# Nano_CAN_shield_v0_1.net
KiCad netlist of a schematic drawn in EAGLE
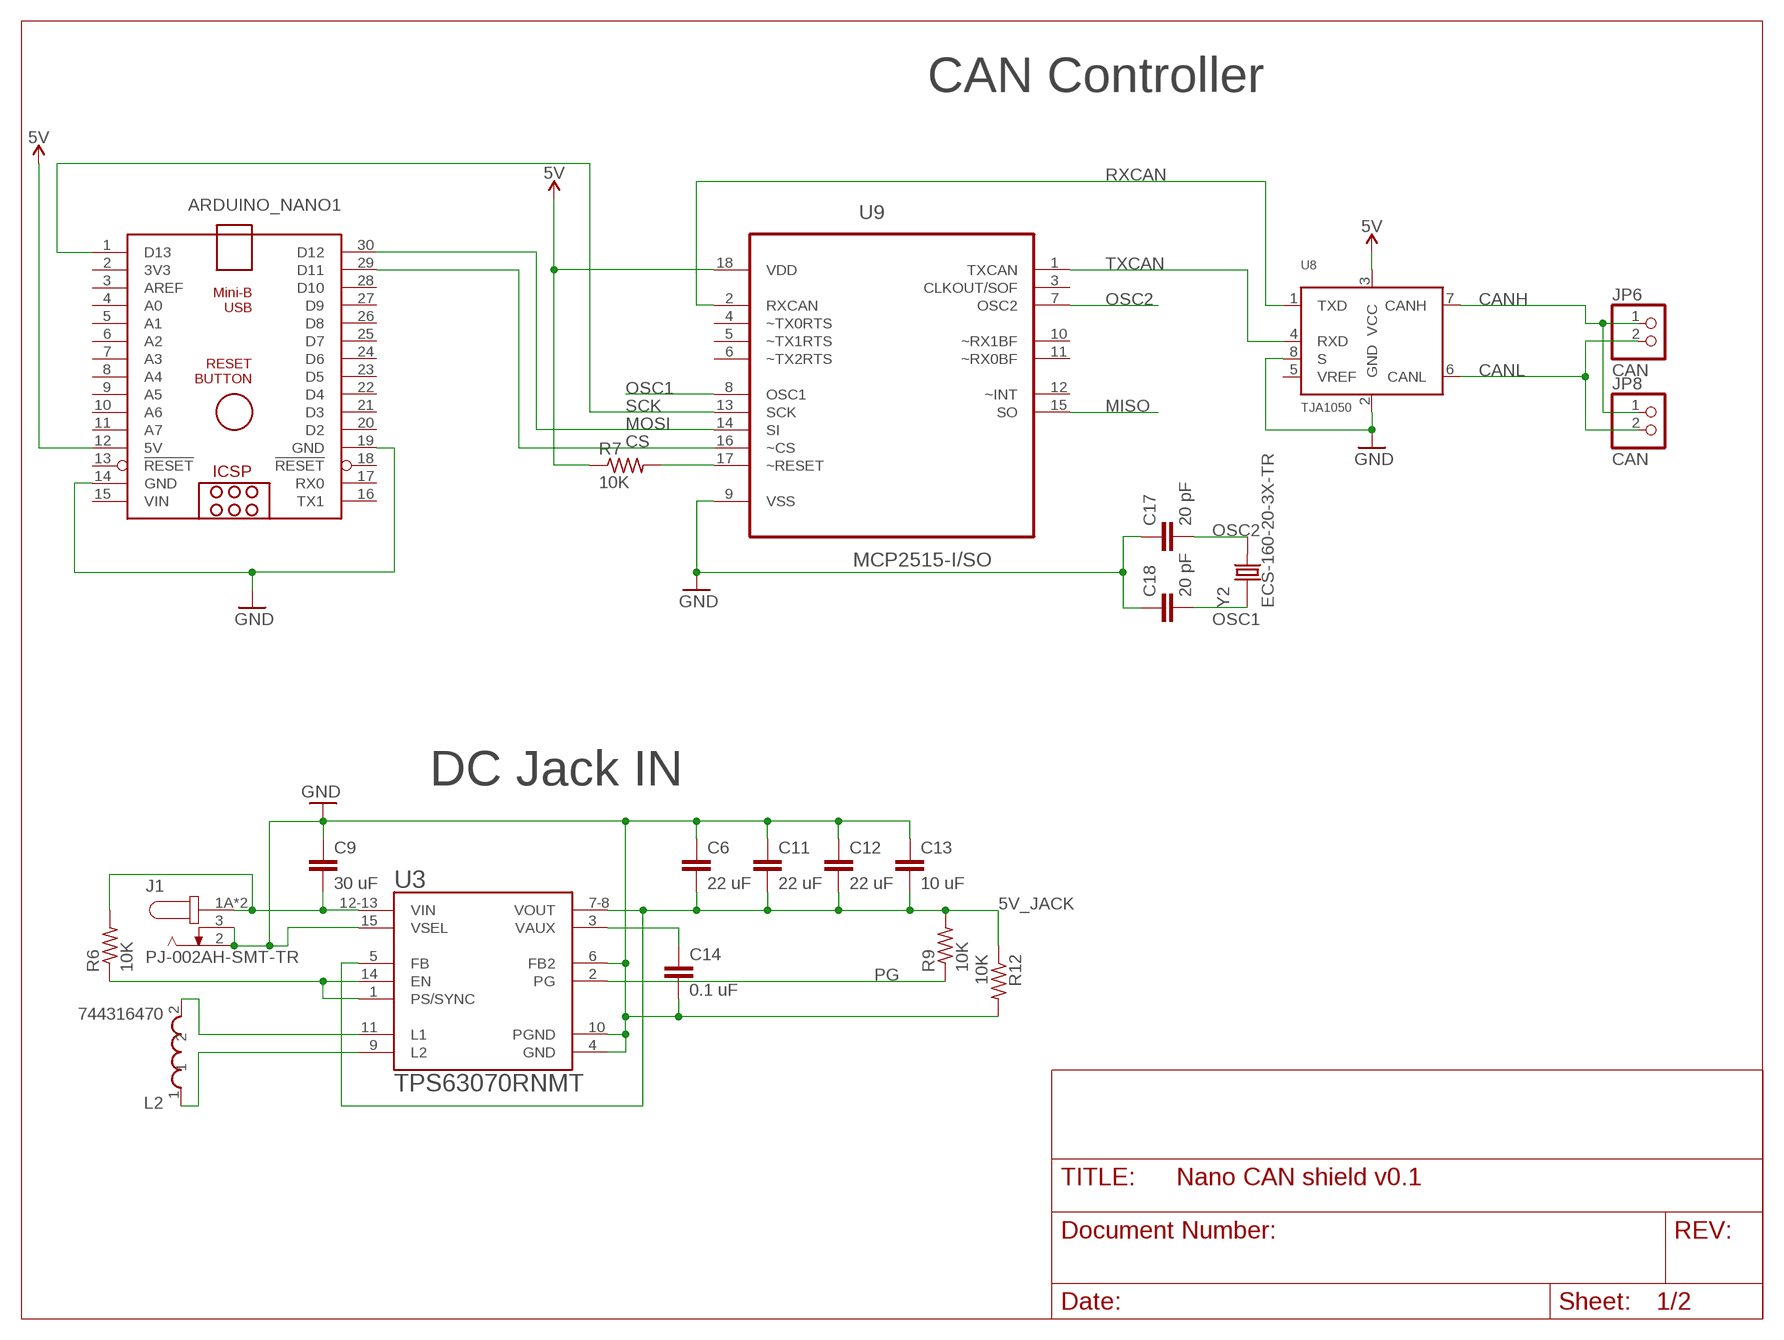
[diagram p0: schematic, sheet 1]
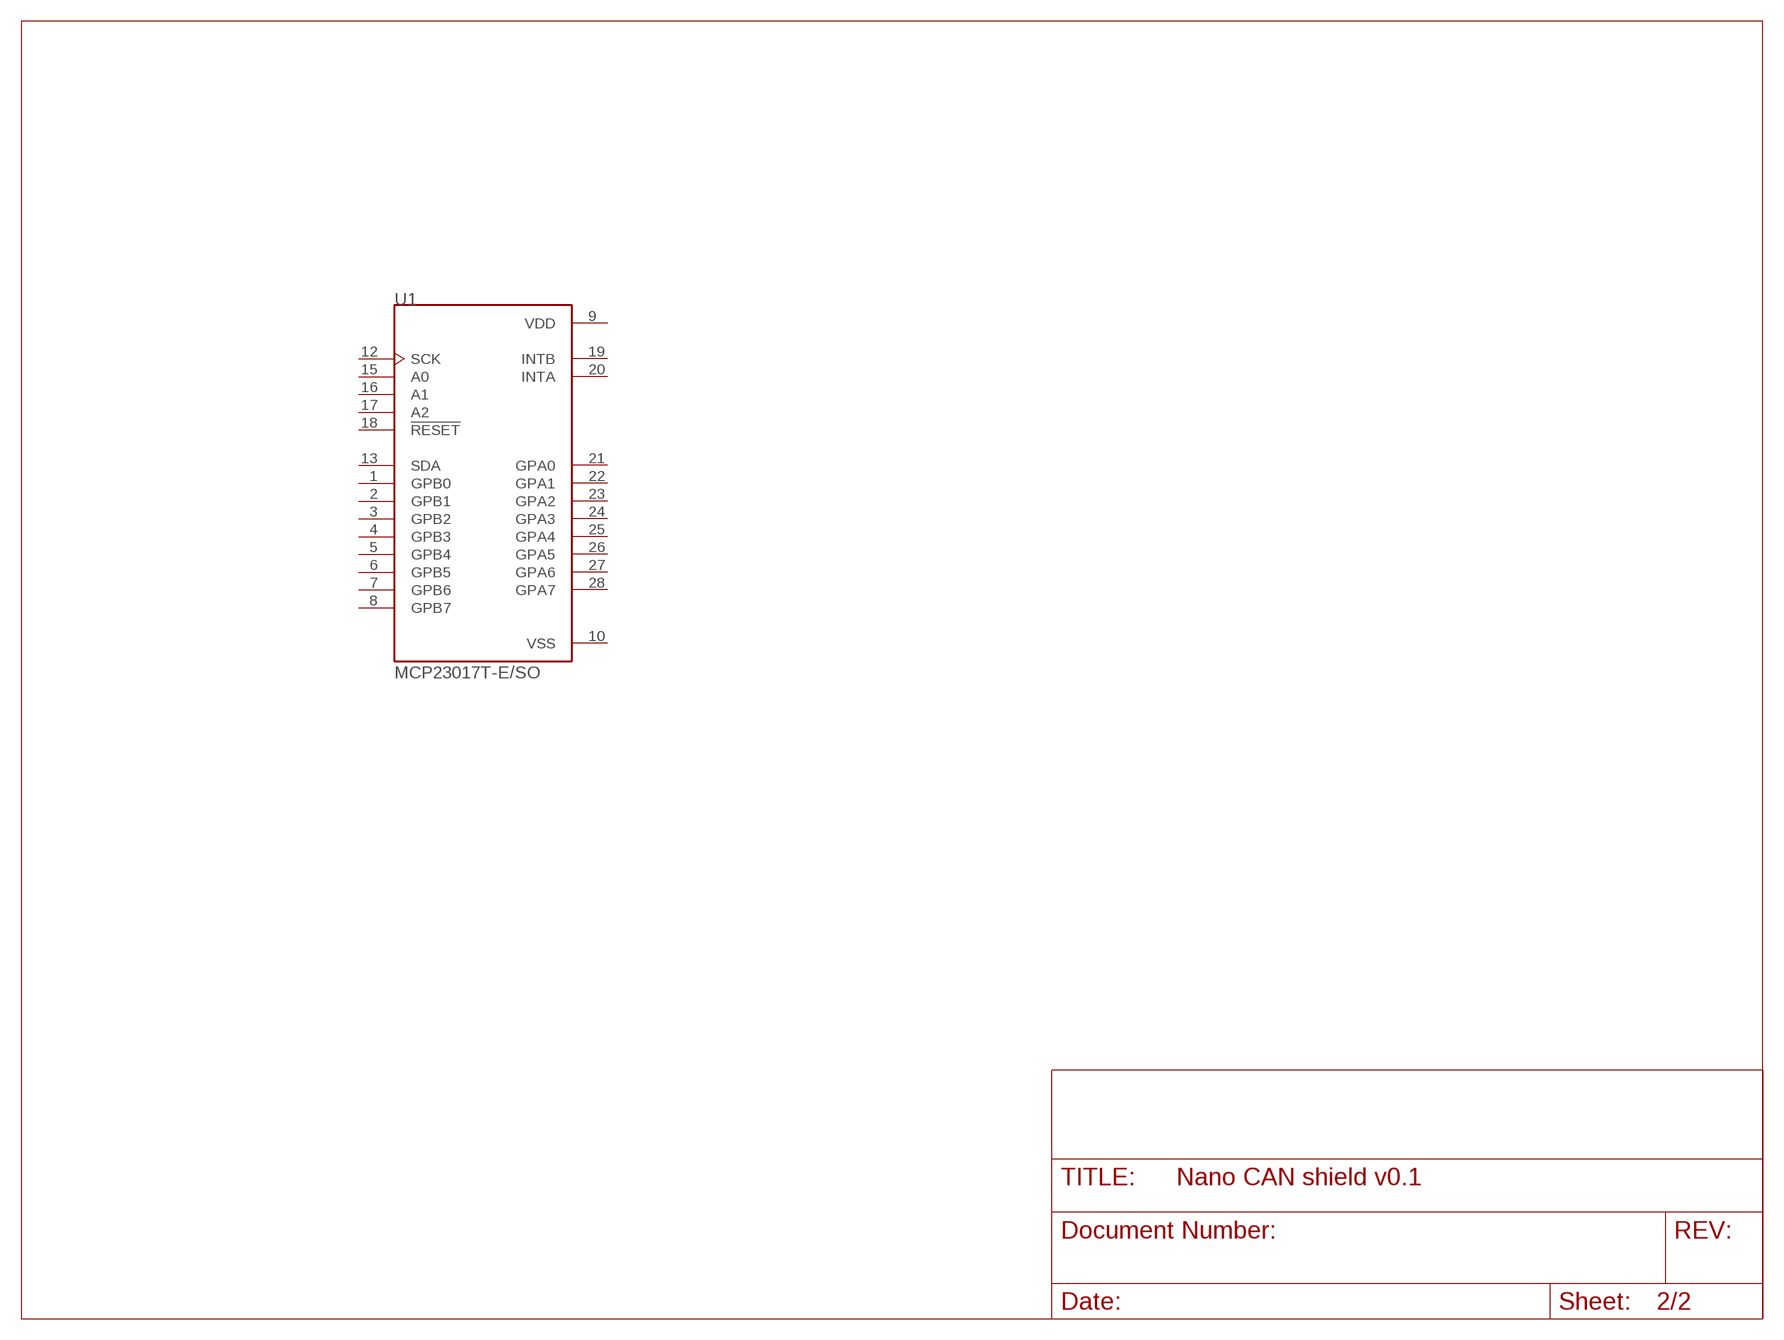
[diagram p1: schematic, sheet 2]

(export (version "E")
  (design (tool "Eeschema 10.0.6"))
  (components
    (comp (ref "ARDUINO_NANO1")
      (value "ARDUINO_NANO")
      (footprint "eagle-import:ARDUINO_NANO")
      (libsource (lib "eagle-import") (part "ARDUINO_NANO"))
    )
    (comp (ref "C6")
      (value "22 uF")
      (footprint "eagle-import:C0603")
      (libsource (lib "eagle-import") (part "C-EUC0603"))
    )
    (comp (ref "C9")
      (value "30 uF")
      (footprint "eagle-import:C0603")
      (libsource (lib "eagle-import") (part "C-EUC0603"))
    )
    (comp (ref "C11")
      (value "22 uF")
      (footprint "eagle-import:C0603")
      (libsource (lib "eagle-import") (part "C-EUC0603"))
    )
    (comp (ref "C12")
      (value "22 uF")
      (footprint "eagle-import:C0603")
      (libsource (lib "eagle-import") (part "C-EUC0603"))
    )
    (comp (ref "C13")
      (value "10 uF")
      (footprint "eagle-import:C0603")
      (libsource (lib "eagle-import") (part "C-EUC0603"))
    )
    (comp (ref "C14")
      (value "0.1 uF")
      (footprint "eagle-import:C0603")
      (libsource (lib "eagle-import") (part "C-EUC0603"))
    )
    (comp (ref "C17")
      (value "20 pF")
      (footprint "eagle-import:C0603")
      (libsource (lib "eagle-import") (part "C-EUC0603"))
    )
    (comp (ref "C18")
      (value "20 pF")
      (footprint "eagle-import:C0603")
      (libsource (lib "eagle-import") (part "C-EUC0603"))
    )
    (comp (ref "J1")
      (value "PJ-002AH-SMT-TR")
      (footprint "eagle-import:CUI_PJ-002AH-SMT-TR")
      (fields (field (name "DIGI-KEY_PART_NUMBER") "CP-002AHPJCT-ND") (field (name "MF") "CUI Inc."))
      (libsource (lib "eagle-import") (part "PJ-002AH-SMT-TR"))
    )
    (comp (ref "JP6")
      (value "CAN")
      (footprint "eagle-import:1X02")
      (libsource (lib "eagle-import") (part "PINHD-1X2"))
    )
    (comp (ref "JP8")
      (value "CAN")
      (footprint "eagle-import:1X02")
      (libsource (lib "eagle-import") (part "PINHD-1X2"))
    )
    (comp (ref "L2")
      (value "744316470")
      (footprint "eagle-import:INDC2220X16")
      (fields (field (name "MF") "Wurth Electronics"))
      (libsource (lib "eagle-import") (part "744316470"))
    )
    (comp (ref "R6")
      (value "10K")
      (footprint "eagle-import:R0603")
      (libsource (lib "eagle-import") (part "R-US_R0603"))
    )
    (comp (ref "R7")
      (value "10K")
      (footprint "eagle-import:R0603")
      (libsource (lib "eagle-import") (part "R-US_R0603"))
    )
    (comp (ref "R9")
      (value "10K")
      (footprint "eagle-import:R0603")
      (libsource (lib "eagle-import") (part "R-US_R0603"))
    )
    (comp (ref "R12")
      (value "10K")
      (footprint "eagle-import:R0603")
      (libsource (lib "eagle-import") (part "R-US_R0603"))
    )
    (comp (ref "U3")
      (value "TPS63070RNMT")
      (footprint "eagle-import:QFN50P250X300X100-15N")
      (fields (field (name "MF") "Texas Instruments"))
      (libsource (lib "eagle-import") (part "TPS63070RNMT"))
    )
    (comp (ref "U8")
      (value "TJA1050")
      (footprint "eagle-import:SOT96-1")
      (fields (field (name "DIGI-KEY_PART_NUMBER") "568-10292-1-ND") (field (name "MF") "NXP USA"))
      (libsource (lib "eagle-import") (part "TJA1050"))
    )
    (comp (ref "U9")
      (value "MCP2515-I/SO")
      (footprint "eagle-import:SOIC127P1034X264-18N")
      (fields (field (name "DIGI-KEY_PART_NUMBER") "MCP2515-I/SO-ND") (field (name "MF") "Microchip"))
      (libsource (lib "eagle-import") (part "MCP2515-I/SO"))
    )
    (comp (ref "Y2")
      (value "ECS-160-20-3X-TR")
      (footprint "eagle-import:XTAL_ECS-160-20-3X-TR")
      (fields (field (name "MF") "ECS Inc."))
      (libsource (lib "eagle-import") (part "ECS-160-20-3X-TR"))
    )
    (comp (ref "U1")
      (value "MCP23017T-E/SO")
      (footprint "eagle-import:SOIC127P1030X265-28N")
      (fields (field (name "DIGI-KEY_PART_NUMBER") "MCP23017T-E/SOCT-ND") (field (name "MF") "Microchip"))
      (libsource (lib "eagle-import") (part "MCP23017T-E/SO"))
    )
  )
  (nets
    (net (code "1") (name "5V") (class "Default")
      (node (ref "ARDUINO_NANO1") (pin "12") (pinfunction "5V_12") (pintype "power_in"))
      (node (ref "R7") (pin "1") (pinfunction "1_1") (pintype "passive"))
      (node (ref "U8") (pin "3") (pinfunction "VCC_3") (pintype "bidirectional"))
      (node (ref "U9") (pin "18") (pinfunction "VDD_18") (pintype "power_in"))
    )
    (net (code "2") (name "5V_JACK") (class "Default")
      (node (ref "C11") (pin "2") (pinfunction "2_2") (pintype "passive"))
      (node (ref "C12") (pin "2") (pinfunction "2_2") (pintype "passive"))
      (node (ref "C13") (pin "2") (pinfunction "2_2") (pintype "passive"))
      (node (ref "C6") (pin "2") (pinfunction "2_2") (pintype "passive"))
      (node (ref "R12") (pin "1") (pinfunction "1_1") (pintype "passive"))
      (node (ref "R9") (pin "2") (pinfunction "2_2") (pintype "passive"))
      (node (ref "U3") (pin "5") (pinfunction "FB_5") (pintype "input"))
      (node (ref "U3") (pin "7-8") (pinfunction "VOUT_7-8") (pintype "output"))
    )
    (net (code "3") (name "CANH") (class "Default")
      (node (ref "JP6") (pin "1") (pinfunction "1_1") (pintype "passive"))
      (node (ref "JP8") (pin "1") (pinfunction "1_1") (pintype "passive"))
      (node (ref "U8") (pin "7") (pinfunction "CANH_7") (pintype "bidirectional"))
    )
    (net (code "4") (name "CANL") (class "Default")
      (node (ref "JP6") (pin "2") (pinfunction "2_2") (pintype "passive"))
      (node (ref "JP8") (pin "2") (pinfunction "2_2") (pintype "passive"))
      (node (ref "U8") (pin "6") (pinfunction "CANL_6") (pintype "bidirectional"))
    )
    (net (code "5") (name "CS") (class "Default")
      (node (ref "ARDUINO_NANO1") (pin "29") (pinfunction "D11_29") (pintype "bidirectional"))
      (node (ref "U9") (pin "16") (pinfunction "~{CS}_16") (pintype "input"))
    )
    (net (code "6") (name "GND") (class "Default")
      (node (ref "ARDUINO_NANO1") (pin "14") (pinfunction "GND_14") (pintype "power_in"))
      (node (ref "ARDUINO_NANO1") (pin "19") (pinfunction "GND_19") (pintype "power_in"))
      (node (ref "C11") (pin "1") (pinfunction "1_1") (pintype "passive"))
      (node (ref "C12") (pin "1") (pinfunction "1_1") (pintype "passive"))
      (node (ref "C13") (pin "1") (pinfunction "1_1") (pintype "passive"))
      (node (ref "C14") (pin "2") (pinfunction "2_2") (pintype "passive"))
      (node (ref "C17") (pin "1") (pinfunction "1_1") (pintype "passive"))
      (node (ref "C18") (pin "1") (pinfunction "1_1") (pintype "passive"))
      (node (ref "C6") (pin "1") (pinfunction "1_1") (pintype "passive"))
      (node (ref "C9") (pin "1") (pinfunction "1_1") (pintype "passive"))
      (node (ref "J1") (pin "2") (pinfunction "2_2") (pintype "passive"))
      (node (ref "J1") (pin "3") (pinfunction "3_3") (pintype "passive"))
      (node (ref "R12") (pin "2") (pinfunction "2_2") (pintype "passive"))
      (node (ref "U3") (pin "10") (pinfunction "PGND_10") (pintype "power_in"))
      (node (ref "U3") (pin "15") (pinfunction "VSEL_15") (pintype "input"))
      (node (ref "U3") (pin "4") (pinfunction "GND_4") (pintype "power_in"))
      (node (ref "U3") (pin "6") (pinfunction "FB2_6") (pintype "output"))
      (node (ref "U8") (pin "2") (pinfunction "GND_2") (pintype "bidirectional"))
      (node (ref "U8") (pin "8") (pinfunction "S_8") (pintype "power_in"))
      (node (ref "U9") (pin "9") (pinfunction "VSS_9") (pintype "power_in"))
    )
    (net (code "7") (name "MISO") (class "Default")
      (node (ref "U9") (pin "15") (pinfunction "SO_15") (pintype "output"))
    )
    (net (code "8") (name "MOSI") (class "Default")
      (node (ref "ARDUINO_NANO1") (pin "30") (pinfunction "D12_30") (pintype "bidirectional"))
      (node (ref "U9") (pin "14") (pinfunction "SI_14") (pintype "input"))
    )
    (net (code "9") (name "Net-(U3-EN)") (class "Default")
      (node (ref "R6") (pin "1") (pinfunction "1_1") (pintype "passive"))
      (node (ref "U3") (pin "1") (pinfunction "PS/SYNC_1") (pintype "input"))
      (node (ref "U3") (pin "14") (pinfunction "EN_14") (pintype "input"))
    )
    (net (code "10") (name "Net-(U3-L1)") (class "Default")
      (node (ref "L2") (pin "2") (pinfunction "2_2") (pintype "passive"))
      (node (ref "U3") (pin "11") (pinfunction "L1_11") (pintype "input"))
    )
    (net (code "11") (name "Net-(U3-L2)") (class "Default")
      (node (ref "L2") (pin "1") (pinfunction "1_1") (pintype "passive"))
      (node (ref "U3") (pin "9") (pinfunction "L2_9") (pintype "input"))
    )
    (net (code "12") (name "Net-(U3-VAUX)") (class "Default")
      (node (ref "C14") (pin "1") (pinfunction "1_1") (pintype "passive"))
      (node (ref "U3") (pin "3") (pinfunction "VAUX_3") (pintype "output"))
    )
    (net (code "13") (name "Net-(U3-VIN)") (class "Default")
      (node (ref "C9") (pin "2") (pinfunction "2_2") (pintype "passive"))
      (node (ref "J1") (pin "1A") (pinfunction "1_1A") (pintype "passive"))
      (node (ref "J1") (pin "1B") (pinfunction "1_1B") (pintype "passive"))
      (node (ref "R6") (pin "2") (pinfunction "2_2") (pintype "passive"))
      (node (ref "U3") (pin "12-13") (pinfunction "VIN_12-13") (pintype "input"))
    )
    (net (code "14") (name "Net-(U9-~{RESET})") (class "Default")
      (node (ref "R7") (pin "2") (pinfunction "2_2") (pintype "passive"))
      (node (ref "U9") (pin "17") (pinfunction "~{RESET}_17") (pintype "input"))
    )
    (net (code "15") (name "OSC1") (class "Default")
      (node (ref "C18") (pin "2") (pinfunction "2_2") (pintype "passive"))
      (node (ref "U9") (pin "8") (pinfunction "OSC1_8") (pintype "input"))
      (node (ref "Y2") (pin "1") (pinfunction "1_1") (pintype "passive"))
    )
    (net (code "16") (name "OSC2") (class "Default")
      (node (ref "C17") (pin "2") (pinfunction "2_2") (pintype "passive"))
      (node (ref "U9") (pin "7") (pinfunction "OSC2_7") (pintype "output"))
      (node (ref "Y2") (pin "2") (pinfunction "2_2") (pintype "passive"))
    )
    (net (code "17") (name "PG") (class "Default")
      (node (ref "R9") (pin "1") (pinfunction "1_1") (pintype "passive"))
      (node (ref "U3") (pin "2") (pinfunction "PG_2") (pintype "output"))
    )
    (net (code "18") (name "RXCAN") (class "Default")
      (node (ref "U8") (pin "1") (pinfunction "TXD_1") (pintype "output"))
      (node (ref "U9") (pin "2") (pinfunction "RXCAN_2") (pintype "input"))
    )
    (net (code "19") (name "SCK") (class "Default")
      (node (ref "ARDUINO_NANO1") (pin "1") (pinfunction "D13_1") (pintype "bidirectional"))
      (node (ref "U9") (pin "13") (pinfunction "SCK_13") (pintype "input"))
    )
    (net (code "20") (name "TXCAN") (class "Default")
      (node (ref "U8") (pin "4") (pinfunction "RXD_4") (pintype "bidirectional"))
      (node (ref "U9") (pin "1") (pinfunction "TXCAN_1") (pintype "output"))
    )
    (net (code "21") (name "VDD") (class "Default")
      (node (ref "U1") (pin "9") (pinfunction "VDD_9") (pintype "power_in"))
    )
    (net (code "22") (name "VIN") (class "Default")
      (node (ref "ARDUINO_NANO1") (pin "15") (pinfunction "VIN_15") (pintype "power_in"))
    )
    (net (code "23") (name "VSS") (class "Default")
      (node (ref "U1") (pin "10") (pinfunction "VSS_10") (pintype "power_in"))
    )
    (net (code "24") (name "unconnected-(ARDUINO_NANO1-3V3-Pad2)") (class "Default")
      (node (ref "ARDUINO_NANO1") (pin "2") (pinfunction "3V3_2") (pintype "output"))
    )
    (net (code "25") (name "unconnected-(ARDUINO_NANO1-A0-Pad4)") (class "Default")
      (node (ref "ARDUINO_NANO1") (pin "4") (pinfunction "A0_4") (pintype "bidirectional"))
    )
    (net (code "26") (name "unconnected-(ARDUINO_NANO1-A1-Pad5)") (class "Default")
      (node (ref "ARDUINO_NANO1") (pin "5") (pinfunction "A1_5") (pintype "bidirectional"))
    )
    (net (code "27") (name "unconnected-(ARDUINO_NANO1-A2-Pad6)") (class "Default")
      (node (ref "ARDUINO_NANO1") (pin "6") (pinfunction "A2_6") (pintype "bidirectional"))
    )
    (net (code "28") (name "unconnected-(ARDUINO_NANO1-A3-Pad7)") (class "Default")
      (node (ref "ARDUINO_NANO1") (pin "7") (pinfunction "A3_7") (pintype "bidirectional"))
    )
    (net (code "29") (name "unconnected-(ARDUINO_NANO1-A4-Pad8)") (class "Default")
      (node (ref "ARDUINO_NANO1") (pin "8") (pinfunction "A4_8") (pintype "bidirectional"))
    )
    (net (code "30") (name "unconnected-(ARDUINO_NANO1-A5-Pad9)") (class "Default")
      (node (ref "ARDUINO_NANO1") (pin "9") (pinfunction "A5_9") (pintype "bidirectional"))
    )
    (net (code "31") (name "unconnected-(ARDUINO_NANO1-A6-Pad10)") (class "Default")
      (node (ref "ARDUINO_NANO1") (pin "10") (pinfunction "A6_10") (pintype "bidirectional"))
    )
    (net (code "32") (name "unconnected-(ARDUINO_NANO1-A7-Pad11)") (class "Default")
      (node (ref "ARDUINO_NANO1") (pin "11") (pinfunction "A7_11") (pintype "bidirectional"))
    )
    (net (code "33") (name "unconnected-(ARDUINO_NANO1-AREF-Pad3)") (class "Default")
      (node (ref "ARDUINO_NANO1") (pin "3") (pinfunction "AREF_3") (pintype "input"))
    )
    (net (code "34") (name "unconnected-(ARDUINO_NANO1-D2-Pad20)") (class "Default")
      (node (ref "ARDUINO_NANO1") (pin "20") (pinfunction "D2_20") (pintype "bidirectional"))
    )
    (net (code "35") (name "unconnected-(ARDUINO_NANO1-D3-Pad21)") (class "Default")
      (node (ref "ARDUINO_NANO1") (pin "21") (pinfunction "D3_21") (pintype "bidirectional"))
    )
    (net (code "36") (name "unconnected-(ARDUINO_NANO1-D4-Pad22)") (class "Default")
      (node (ref "ARDUINO_NANO1") (pin "22") (pinfunction "D4_22") (pintype "bidirectional"))
    )
    (net (code "37") (name "unconnected-(ARDUINO_NANO1-D5-Pad23)") (class "Default")
      (node (ref "ARDUINO_NANO1") (pin "23") (pinfunction "D5_23") (pintype "bidirectional"))
    )
    (net (code "38") (name "unconnected-(ARDUINO_NANO1-D6-Pad24)") (class "Default")
      (node (ref "ARDUINO_NANO1") (pin "24") (pinfunction "D6_24") (pintype "bidirectional"))
    )
    (net (code "39") (name "unconnected-(ARDUINO_NANO1-D7-Pad25)") (class "Default")
      (node (ref "ARDUINO_NANO1") (pin "25") (pinfunction "D7_25") (pintype "bidirectional"))
    )
    (net (code "40") (name "unconnected-(ARDUINO_NANO1-D8-Pad26)") (class "Default")
      (node (ref "ARDUINO_NANO1") (pin "26") (pinfunction "D8_26") (pintype "bidirectional"))
    )
    (net (code "41") (name "unconnected-(ARDUINO_NANO1-D9-Pad27)") (class "Default")
      (node (ref "ARDUINO_NANO1") (pin "27") (pinfunction "D9_27") (pintype "bidirectional"))
    )
    (net (code "42") (name "unconnected-(ARDUINO_NANO1-D10-Pad28)") (class "Default")
      (node (ref "ARDUINO_NANO1") (pin "28") (pinfunction "D10_28") (pintype "bidirectional"))
    )
    (net (code "43") (name "unconnected-(ARDUINO_NANO1-RX0-Pad17)") (class "Default")
      (node (ref "ARDUINO_NANO1") (pin "17") (pinfunction "RX0_17") (pintype "bidirectional"))
    )
    (net (code "44") (name "unconnected-(ARDUINO_NANO1-TX1-Pad16)") (class "Default")
      (node (ref "ARDUINO_NANO1") (pin "16") (pinfunction "TX1_16") (pintype "bidirectional"))
    )
    (net (code "45") (name "unconnected-(ARDUINO_NANO1-~{RESET}-Pad13)") (class "Default")
      (node (ref "ARDUINO_NANO1") (pin "13") (pinfunction "~{RESET}_13") (pintype "input"))
    )
    (net (code "46") (name "unconnected-(ARDUINO_NANO1-~{RESET}-Pad18)") (class "Default")
      (node (ref "ARDUINO_NANO1") (pin "18") (pinfunction "~{RESET}_18") (pintype "input"))
    )
    (net (code "47") (name "unconnected-(U1-A0-Pad15)") (class "Default")
      (node (ref "U1") (pin "15") (pinfunction "A0_15") (pintype "input"))
    )
    (net (code "48") (name "unconnected-(U1-A1-Pad16)") (class "Default")
      (node (ref "U1") (pin "16") (pinfunction "A1_16") (pintype "input"))
    )
    (net (code "49") (name "unconnected-(U1-A2-Pad17)") (class "Default")
      (node (ref "U1") (pin "17") (pinfunction "A2_17") (pintype "input"))
    )
    (net (code "50") (name "unconnected-(U1-GPA0-Pad21)") (class "Default")
      (node (ref "U1") (pin "21") (pinfunction "GPA0_21") (pintype "bidirectional"))
    )
    (net (code "51") (name "unconnected-(U1-GPA1-Pad22)") (class "Default")
      (node (ref "U1") (pin "22") (pinfunction "GPA1_22") (pintype "bidirectional"))
    )
    (net (code "52") (name "unconnected-(U1-GPA2-Pad23)") (class "Default")
      (node (ref "U1") (pin "23") (pinfunction "GPA2_23") (pintype "bidirectional"))
    )
    (net (code "53") (name "unconnected-(U1-GPA3-Pad24)") (class "Default")
      (node (ref "U1") (pin "24") (pinfunction "GPA3_24") (pintype "bidirectional"))
    )
    (net (code "54") (name "unconnected-(U1-GPA4-Pad25)") (class "Default")
      (node (ref "U1") (pin "25") (pinfunction "GPA4_25") (pintype "bidirectional"))
    )
    (net (code "55") (name "unconnected-(U1-GPA5-Pad26)") (class "Default")
      (node (ref "U1") (pin "26") (pinfunction "GPA5_26") (pintype "bidirectional"))
    )
    (net (code "56") (name "unconnected-(U1-GPA6-Pad27)") (class "Default")
      (node (ref "U1") (pin "27") (pinfunction "GPA6_27") (pintype "bidirectional"))
    )
    (net (code "57") (name "unconnected-(U1-GPA7-Pad28)") (class "Default")
      (node (ref "U1") (pin "28") (pinfunction "GPA7_28") (pintype "bidirectional"))
    )
    (net (code "58") (name "unconnected-(U1-GPB0-Pad1)") (class "Default")
      (node (ref "U1") (pin "1") (pinfunction "GPB0_1") (pintype "bidirectional"))
    )
    (net (code "59") (name "unconnected-(U1-GPB1-Pad2)") (class "Default")
      (node (ref "U1") (pin "2") (pinfunction "GPB1_2") (pintype "bidirectional"))
    )
    (net (code "60") (name "unconnected-(U1-GPB2-Pad3)") (class "Default")
      (node (ref "U1") (pin "3") (pinfunction "GPB2_3") (pintype "bidirectional"))
    )
    (net (code "61") (name "unconnected-(U1-GPB3-Pad4)") (class "Default")
      (node (ref "U1") (pin "4") (pinfunction "GPB3_4") (pintype "bidirectional"))
    )
    (net (code "62") (name "unconnected-(U1-GPB4-Pad5)") (class "Default")
      (node (ref "U1") (pin "5") (pinfunction "GPB4_5") (pintype "bidirectional"))
    )
    (net (code "63") (name "unconnected-(U1-GPB5-Pad6)") (class "Default")
      (node (ref "U1") (pin "6") (pinfunction "GPB5_6") (pintype "bidirectional"))
    )
    (net (code "64") (name "unconnected-(U1-GPB6-Pad7)") (class "Default")
      (node (ref "U1") (pin "7") (pinfunction "GPB6_7") (pintype "bidirectional"))
    )
    (net (code "65") (name "unconnected-(U1-GPB7-Pad8)") (class "Default")
      (node (ref "U1") (pin "8") (pinfunction "GPB7_8") (pintype "bidirectional"))
    )
    (net (code "66") (name "unconnected-(U1-INTA-Pad20)") (class "Default")
      (node (ref "U1") (pin "20") (pinfunction "INTA_20") (pintype "output"))
    )
    (net (code "67") (name "unconnected-(U1-INTB-Pad19)") (class "Default")
      (node (ref "U1") (pin "19") (pinfunction "INTB_19") (pintype "output"))
    )
    (net (code "68") (name "unconnected-(U1-SCK-Pad12)") (class "Default")
      (node (ref "U1") (pin "12") (pinfunction "SCK_12") (pintype "input"))
    )
    (net (code "69") (name "unconnected-(U1-SDA-Pad13)") (class "Default")
      (node (ref "U1") (pin "13") (pinfunction "SDA_13") (pintype "bidirectional"))
    )
    (net (code "70") (name "unconnected-(U1-~{RESET}-Pad18)") (class "Default")
      (node (ref "U1") (pin "18") (pinfunction "~{RESET}_18") (pintype "input"))
    )
    (net (code "71") (name "unconnected-(U8-VREF-Pad5)") (class "Default")
      (node (ref "U8") (pin "5") (pinfunction "VREF_5") (pintype "passive"))
    )
    (net (code "72") (name "unconnected-(U9-CLKOUT{slash}SOF-Pad3)") (class "Default")
      (node (ref "U9") (pin "3") (pinfunction "CLKOUT/SOF_3") (pintype "output"))
    )
    (net (code "73") (name "unconnected-(U9-~{INT}-Pad12)") (class "Default")
      (node (ref "U9") (pin "12") (pinfunction "~{INT}_12") (pintype "output"))
    )
    (net (code "74") (name "unconnected-(U9-~{RX0BF}-Pad11)") (class "Default")
      (node (ref "U9") (pin "11") (pinfunction "~{RX0BF}_11") (pintype "output"))
    )
    (net (code "75") (name "unconnected-(U9-~{RX1BF}-Pad10)") (class "Default")
      (node (ref "U9") (pin "10") (pinfunction "~{RX1BF}_10") (pintype "output"))
    )
    (net (code "76") (name "unconnected-(U9-~{TX0RTS}-Pad4)") (class "Default")
      (node (ref "U9") (pin "4") (pinfunction "~{TX0RTS}_4") (pintype "input"))
    )
    (net (code "77") (name "unconnected-(U9-~{TX1RTS}-Pad5)") (class "Default")
      (node (ref "U9") (pin "5") (pinfunction "~{TX1RTS}_5") (pintype "input"))
    )
    (net (code "78") (name "unconnected-(U9-~{TX2RTS}-Pad6)") (class "Default")
      (node (ref "U9") (pin "6") (pinfunction "~{TX2RTS}_6") (pintype "input"))
    )
  )
)
